# usbtin_clone.net
KiCad netlist of a schematic drawn in EAGLE
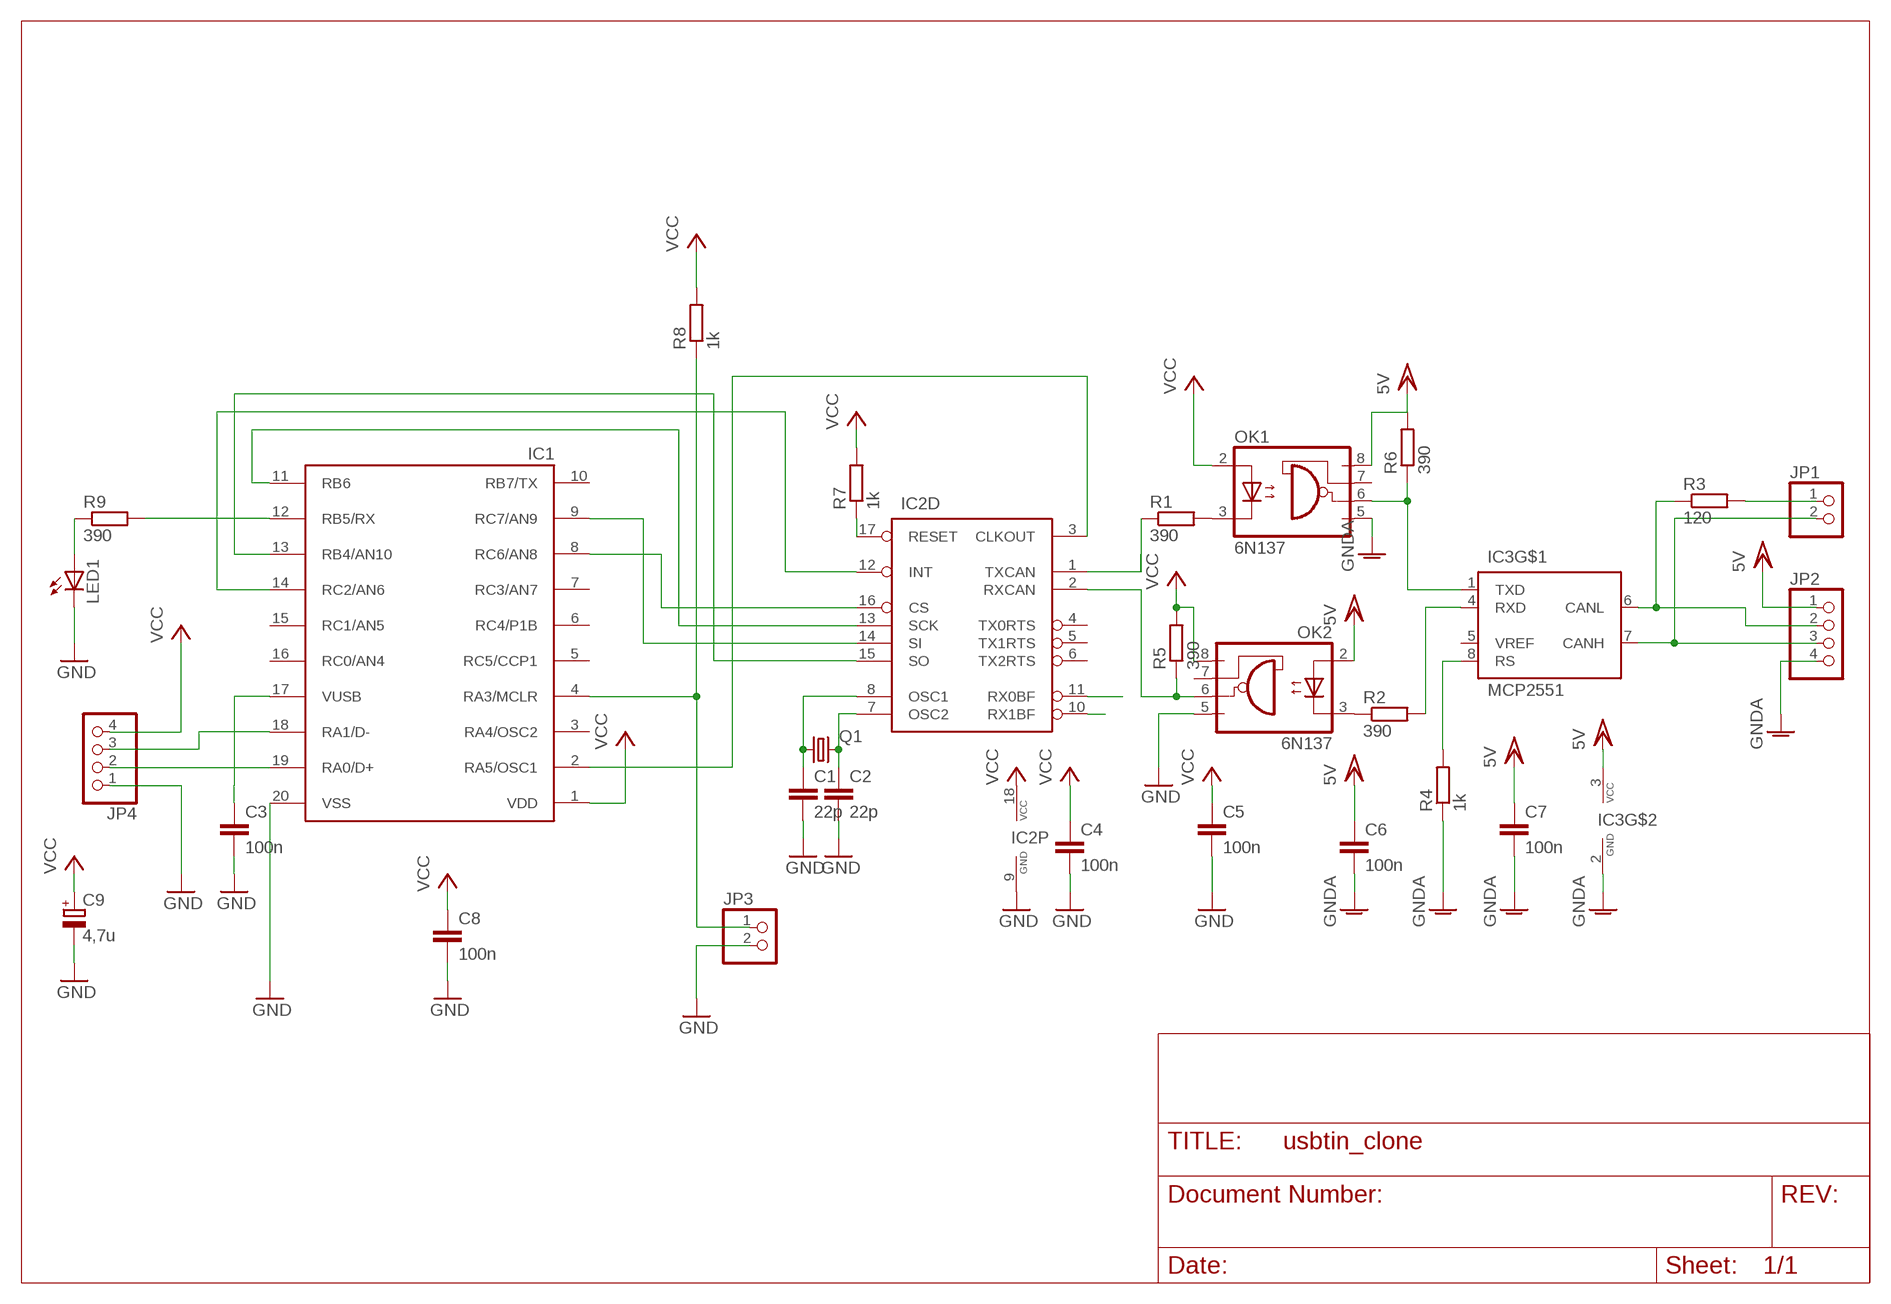
[diagram p0: schematic, sheet 1]

(export (version "E")
  (design (tool "Eeschema 10.0.6"))
  (components
    (comp (ref "C1")
      (value "22p")
      (footprint "eagle-import:C025-025X050")
      (libsource (lib "eagle-import") (part "C-EU025-025X050"))
    )
    (comp (ref "C2")
      (value "22p")
      (footprint "eagle-import:C025-025X050")
      (libsource (lib "eagle-import") (part "C-EU025-025X050"))
    )
    (comp (ref "C3")
      (value "100n")
      (footprint "eagle-import:C025-025X050")
      (libsource (lib "eagle-import") (part "C-EU025-025X050"))
    )
    (comp (ref "C4")
      (value "100n")
      (footprint "eagle-import:C025-025X050")
      (libsource (lib "eagle-import") (part "C-EU025-025X050"))
    )
    (comp (ref "C5")
      (value "100n")
      (footprint "eagle-import:C025-025X050")
      (libsource (lib "eagle-import") (part "C-EU025-025X050"))
    )
    (comp (ref "C6")
      (value "100n")
      (footprint "eagle-import:C025-025X050")
      (libsource (lib "eagle-import") (part "C-EU025-025X050"))
    )
    (comp (ref "C7")
      (value "100n")
      (footprint "eagle-import:C025-025X050")
      (libsource (lib "eagle-import") (part "C-EU025-025X050"))
    )
    (comp (ref "C8")
      (value "100n")
      (footprint "eagle-import:C025-025X050")
      (libsource (lib "eagle-import") (part "C-EU025-025X050"))
    )
    (comp (ref "C9")
      (value "4,7u")
      (footprint "eagle-import:E2,5-5")
      (libsource (lib "eagle-import") (part "CPOL-EUE2.5-5"))
    )
    (comp (ref "IC1")
      (value "18F14K50")
      (footprint "eagle-import:DIL20")
      (libsource (lib "eagle-import") (part "PIC18F14K50"))
    )
    (comp (ref "IC2")
      (value "MCP2515P")
      (footprint "eagle-import:DIL18")
      (libsource (lib "eagle-import") (part "MCP2515P"))
    )
    (comp (ref "IC3")
      (value "MCP2551")
      (footprint "eagle-import:DIL08")
      (libsource (lib "eagle-import") (part "MCP2551DIL8"))
    )
    (comp (ref "JP1")
      (value "PINHD-1X2")
      (footprint "eagle-import:1X02")
      (libsource (lib "eagle-import") (part "PINHD-1X2"))
    )
    (comp (ref "JP2")
      (value "PINHD-1X4")
      (footprint "eagle-import:1X04")
      (libsource (lib "eagle-import") (part "PINHD-1X4"))
    )
    (comp (ref "JP3")
      (value "PINHD-1X2")
      (footprint "eagle-import:1X02")
      (libsource (lib "eagle-import") (part "PINHD-1X2"))
    )
    (comp (ref "JP4")
      (value "PINHD-1X4")
      (footprint "eagle-import:1X04")
      (libsource (lib "eagle-import") (part "PINHD-1X4"))
    )
    (comp (ref "LED1")
      (value "LED3MM")
      (footprint "eagle-import:LED3MM")
      (libsource (lib "eagle-import") (part "LED3MM"))
    )
    (comp (ref "OK1")
      (value "6N137")
      (footprint "eagle-import:DIL08")
      (libsource (lib "eagle-import") (part "6N137"))
    )
    (comp (ref "OK2")
      (value "6N137")
      (footprint "eagle-import:DIL08")
      (libsource (lib "eagle-import") (part "6N137"))
    )
    (comp (ref "Q1")
      (value "CRYSTALHC49S")
      (footprint "eagle-import:HC49_S")
      (libsource (lib "eagle-import") (part "CRYSTALHC49S"))
    )
    (comp (ref "R1")
      (value "390")
      (footprint "eagle-import:0204_7")
      (libsource (lib "eagle-import") (part "R-EU_0204/7"))
    )
    (comp (ref "R2")
      (value "390")
      (footprint "eagle-import:0204_7")
      (libsource (lib "eagle-import") (part "R-EU_0204/7"))
    )
    (comp (ref "R3")
      (value "120")
      (footprint "eagle-import:0204_7")
      (libsource (lib "eagle-import") (part "R-EU_0204/7"))
    )
    (comp (ref "R4")
      (value "1k")
      (footprint "eagle-import:0204_7")
      (libsource (lib "eagle-import") (part "R-EU_0204/7"))
    )
    (comp (ref "R5")
      (value "390")
      (footprint "eagle-import:0204_7")
      (libsource (lib "eagle-import") (part "R-EU_0204/7"))
    )
    (comp (ref "R6")
      (value "390")
      (footprint "eagle-import:0204_7")
      (libsource (lib "eagle-import") (part "R-EU_0204/7"))
    )
    (comp (ref "R7")
      (value "1k")
      (footprint "eagle-import:0204_7")
      (libsource (lib "eagle-import") (part "R-EU_0204/7"))
    )
    (comp (ref "R8")
      (value "1k")
      (footprint "eagle-import:0204_7")
      (libsource (lib "eagle-import") (part "R-EU_0204/7"))
    )
    (comp (ref "R9")
      (value "390")
      (footprint "eagle-import:0204_7")
      (libsource (lib "eagle-import") (part "R-EU_0204/7"))
    )
  )
  (nets
    (net (code "1") (name "5V") (class "Default")
      (node (ref "C6") (pin "1") (pinfunction "1_1") (pintype "passive"))
      (node (ref "C7") (pin "1") (pinfunction "1_1") (pintype "passive"))
      (node (ref "IC3") (pin "3") (pinfunction "VCC_3") (pintype "power_in"))
      (node (ref "JP2") (pin "1") (pinfunction "1_1") (pintype "passive"))
      (node (ref "OK1") (pin "8") (pinfunction "VCC_8") (pintype "passive"))
      (node (ref "OK2") (pin "2") (pinfunction "A_2") (pintype "passive"))
      (node (ref "R6") (pin "2") (pinfunction "2_2") (pintype "passive"))
    )
    (net (code "2") (name "GND") (class "Default")
      (node (ref "C1") (pin "2") (pinfunction "2_2") (pintype "passive"))
      (node (ref "C2") (pin "2") (pinfunction "2_2") (pintype "passive"))
      (node (ref "C3") (pin "2") (pinfunction "2_2") (pintype "passive"))
      (node (ref "C4") (pin "2") (pinfunction "2_2") (pintype "passive"))
      (node (ref "C5") (pin "2") (pinfunction "2_2") (pintype "passive"))
      (node (ref "C8") (pin "2") (pinfunction "2_2") (pintype "passive"))
      (node (ref "C9") (pin "-") (pinfunction "-_-") (pintype "passive"))
      (node (ref "IC1") (pin "20") (pinfunction "VSS_20") (pintype "bidirectional"))
      (node (ref "IC2") (pin "9") (pinfunction "GND_9") (pintype "power_in"))
      (node (ref "JP3") (pin "2") (pinfunction "2_2") (pintype "passive"))
      (node (ref "JP4") (pin "1") (pinfunction "1_1") (pintype "passive"))
      (node (ref "LED1") (pin "K") (pinfunction "C_K") (pintype "passive"))
      (node (ref "OK2") (pin "5") (pinfunction "GND_5") (pintype "passive"))
    )
    (net (code "3") (name "GNDA") (class "Default")
      (node (ref "C6") (pin "2") (pinfunction "2_2") (pintype "passive"))
      (node (ref "C7") (pin "2") (pinfunction "2_2") (pintype "passive"))
      (node (ref "IC3") (pin "2") (pinfunction "GND_2") (pintype "power_in"))
      (node (ref "JP2") (pin "4") (pinfunction "4_4") (pintype "passive"))
      (node (ref "OK1") (pin "5") (pinfunction "GND_5") (pintype "passive"))
      (node (ref "R4") (pin "1") (pinfunction "1_1") (pintype "passive"))
    )
    (net (code "4") (name "Net-(IC1-RA0{slash}D+)") (class "Default")
      (node (ref "IC1") (pin "19") (pinfunction "RA0/D+_19") (pintype "bidirectional"))
      (node (ref "JP4") (pin "2") (pinfunction "2_2") (pintype "passive"))
    )
    (net (code "5") (name "Net-(IC1-RA1{slash}D-)") (class "Default")
      (node (ref "IC1") (pin "18") (pinfunction "RA1/D-_18") (pintype "bidirectional"))
      (node (ref "JP4") (pin "3") (pinfunction "3_3") (pintype "passive"))
    )
    (net (code "6") (name "Net-(IC1-RA3{slash}MCLR)") (class "Default")
      (node (ref "IC1") (pin "4") (pinfunction "RA3/MCLR_4") (pintype "bidirectional"))
      (node (ref "JP3") (pin "1") (pinfunction "1_1") (pintype "passive"))
      (node (ref "R8") (pin "1") (pinfunction "1_1") (pintype "passive"))
    )
    (net (code "7") (name "Net-(IC1-RA5{slash}OSC1)") (class "Default")
      (node (ref "IC1") (pin "2") (pinfunction "RA5/OSC1_2") (pintype "bidirectional"))
      (node (ref "IC2") (pin "3") (pinfunction "CLKOUT_3") (pintype "output"))
    )
    (net (code "8") (name "Net-(IC1-RB4{slash}AN10)") (class "Default")
      (node (ref "IC1") (pin "13") (pinfunction "RB4/AN10_13") (pintype "bidirectional"))
      (node (ref "IC2") (pin "15") (pinfunction "SO_15") (pintype "output"))
    )
    (net (code "9") (name "Net-(IC1-RB5{slash}RX)") (class "Default")
      (node (ref "IC1") (pin "12") (pinfunction "RB5/RX_12") (pintype "bidirectional"))
      (node (ref "R9") (pin "2") (pinfunction "2_2") (pintype "passive"))
    )
    (net (code "10") (name "Net-(IC1-RB6)") (class "Default")
      (node (ref "IC1") (pin "11") (pinfunction "RB6_11") (pintype "bidirectional"))
      (node (ref "IC2") (pin "13") (pinfunction "SCK_13") (pintype "input"))
    )
    (net (code "11") (name "Net-(IC1-RC2{slash}AN6)") (class "Default")
      (node (ref "IC1") (pin "14") (pinfunction "RC2/AN6_14") (pintype "bidirectional"))
      (node (ref "IC2") (pin "12") (pinfunction "INT_12") (pintype "output"))
    )
    (net (code "12") (name "Net-(IC1-RC6{slash}AN8)") (class "Default")
      (node (ref "IC1") (pin "8") (pinfunction "RC6/AN8_8") (pintype "bidirectional"))
      (node (ref "IC2") (pin "16") (pinfunction "CS_16") (pintype "input"))
    )
    (net (code "13") (name "Net-(IC1-RC7{slash}AN9)") (class "Default")
      (node (ref "IC1") (pin "9") (pinfunction "RC7/AN9_9") (pintype "bidirectional"))
      (node (ref "IC2") (pin "14") (pinfunction "SI_14") (pintype "input"))
    )
    (net (code "14") (name "Net-(IC1-VUSB)") (class "Default")
      (node (ref "C3") (pin "1") (pinfunction "1_1") (pintype "passive"))
      (node (ref "IC1") (pin "17") (pinfunction "VUSB_17") (pintype "bidirectional"))
    )
    (net (code "15") (name "Net-(IC2A-OSC1)") (class "Default")
      (node (ref "C1") (pin "1") (pinfunction "1_1") (pintype "passive"))
      (node (ref "IC2") (pin "8") (pinfunction "OSC1_8") (pintype "input"))
      (node (ref "Q1") (pin "1") (pinfunction "1_1") (pintype "passive"))
    )
    (net (code "16") (name "Net-(IC2A-OSC2)") (class "Default")
      (node (ref "C2") (pin "1") (pinfunction "1_1") (pintype "passive"))
      (node (ref "IC2") (pin "7") (pinfunction "OSC2_7") (pintype "input"))
      (node (ref "Q1") (pin "2") (pinfunction "2_2") (pintype "passive"))
    )
    (net (code "17") (name "Net-(IC2A-RESET)") (class "Default")
      (node (ref "IC2") (pin "17") (pinfunction "RESET_17") (pintype "input"))
      (node (ref "R7") (pin "1") (pinfunction "1_1") (pintype "passive"))
    )
    (net (code "18") (name "Net-(IC2A-RXCAN)") (class "Default")
      (node (ref "IC2") (pin "2") (pinfunction "RXCAN_2") (pintype "input"))
      (node (ref "OK2") (pin "6") (pinfunction "VO_6") (pintype "passive"))
      (node (ref "R5") (pin "1") (pinfunction "1_1") (pintype "passive"))
    )
    (net (code "19") (name "Net-(IC2A-TXCAN)") (class "Default")
      (node (ref "IC2") (pin "1") (pinfunction "TXCAN_1") (pintype "output"))
      (node (ref "R1") (pin "1") (pinfunction "1_1") (pintype "passive"))
    )
    (net (code "20") (name "Net-(IC3A-CANH)") (class "Default")
      (node (ref "IC3") (pin "7") (pinfunction "CANH_7") (pintype "bidirectional"))
      (node (ref "JP1") (pin "2") (pinfunction "2_2") (pintype "passive"))
      (node (ref "JP2") (pin "3") (pinfunction "3_3") (pintype "passive"))
    )
    (net (code "21") (name "Net-(IC3A-CANL)") (class "Default")
      (node (ref "IC3") (pin "6") (pinfunction "CANL_6") (pintype "bidirectional"))
      (node (ref "JP2") (pin "2") (pinfunction "2_2") (pintype "passive"))
      (node (ref "R3") (pin "1") (pinfunction "1_1") (pintype "passive"))
    )
    (net (code "22") (name "Net-(IC3A-RS)") (class "Default")
      (node (ref "IC3") (pin "8") (pinfunction "RS_8") (pintype "bidirectional"))
      (node (ref "R4") (pin "2") (pinfunction "2_2") (pintype "passive"))
    )
    (net (code "23") (name "Net-(IC3A-RXD)") (class "Default")
      (node (ref "IC3") (pin "4") (pinfunction "RXD_4") (pintype "bidirectional"))
      (node (ref "R2") (pin "2") (pinfunction "2_2") (pintype "passive"))
    )
    (net (code "24") (name "Net-(IC3A-TXD)") (class "Default")
      (node (ref "IC3") (pin "1") (pinfunction "TXD_1") (pintype "bidirectional"))
      (node (ref "OK1") (pin "6") (pinfunction "VO_6") (pintype "passive"))
      (node (ref "R6") (pin "1") (pinfunction "1_1") (pintype "passive"))
    )
    (net (code "25") (name "Net-(JP1-Pad1)") (class "Default")
      (node (ref "JP1") (pin "1") (pinfunction "1_1") (pintype "passive"))
      (node (ref "R3") (pin "2") (pinfunction "2_2") (pintype "passive"))
    )
    (net (code "26") (name "Net-(LED1-PadA)") (class "Default")
      (node (ref "LED1") (pin "A") (pinfunction "A_A") (pintype "passive"))
      (node (ref "R9") (pin "1") (pinfunction "1_1") (pintype "passive"))
    )
    (net (code "27") (name "Net-(OK1-C)") (class "Default")
      (node (ref "OK1") (pin "3") (pinfunction "C_3") (pintype "passive"))
      (node (ref "R1") (pin "2") (pinfunction "2_2") (pintype "passive"))
    )
    (net (code "28") (name "Net-(OK2-C)") (class "Default")
      (node (ref "OK2") (pin "3") (pinfunction "C_3") (pintype "passive"))
      (node (ref "R2") (pin "1") (pinfunction "1_1") (pintype "passive"))
    )
    (net (code "29") (name "VCC") (class "Default")
      (node (ref "C4") (pin "1") (pinfunction "1_1") (pintype "passive"))
      (node (ref "C5") (pin "1") (pinfunction "1_1") (pintype "passive"))
      (node (ref "C8") (pin "1") (pinfunction "1_1") (pintype "passive"))
      (node (ref "C9") (pin "+") (pinfunction "+_+") (pintype "passive"))
      (node (ref "IC1") (pin "1") (pinfunction "VDD_1") (pintype "bidirectional"))
      (node (ref "IC2") (pin "18") (pinfunction "VCC_18") (pintype "power_in"))
      (node (ref "JP4") (pin "4") (pinfunction "4_4") (pintype "passive"))
      (node (ref "OK1") (pin "2") (pinfunction "A_2") (pintype "passive"))
      (node (ref "OK2") (pin "8") (pinfunction "VCC_8") (pintype "passive"))
      (node (ref "R5") (pin "2") (pinfunction "2_2") (pintype "passive"))
      (node (ref "R7") (pin "2") (pinfunction "2_2") (pintype "passive"))
      (node (ref "R8") (pin "2") (pinfunction "2_2") (pintype "passive"))
    )
    (net (code "30") (name "unconnected-(IC1-RA4{slash}OSC2-Pad3)") (class "Default")
      (node (ref "IC1") (pin "3") (pinfunction "RA4/OSC2_3") (pintype "bidirectional"))
    )
    (net (code "31") (name "unconnected-(IC1-RB7{slash}TX-Pad10)") (class "Default")
      (node (ref "IC1") (pin "10") (pinfunction "RB7/TX_10") (pintype "bidirectional"))
    )
    (net (code "32") (name "unconnected-(IC1-RC0{slash}AN4-Pad16)") (class "Default")
      (node (ref "IC1") (pin "16") (pinfunction "RC0/AN4_16") (pintype "bidirectional"))
    )
    (net (code "33") (name "unconnected-(IC1-RC1{slash}AN5-Pad15)") (class "Default")
      (node (ref "IC1") (pin "15") (pinfunction "RC1/AN5_15") (pintype "bidirectional"))
    )
    (net (code "34") (name "unconnected-(IC1-RC3{slash}AN7-Pad7)") (class "Default")
      (node (ref "IC1") (pin "7") (pinfunction "RC3/AN7_7") (pintype "bidirectional"))
    )
    (net (code "35") (name "unconnected-(IC1-RC4{slash}P1B-Pad6)") (class "Default")
      (node (ref "IC1") (pin "6") (pinfunction "RC4/P1B_6") (pintype "bidirectional"))
    )
    (net (code "36") (name "unconnected-(IC1-RC5{slash}CCP1-Pad5)") (class "Default")
      (node (ref "IC1") (pin "5") (pinfunction "RC5/CCP1_5") (pintype "bidirectional"))
    )
    (net (code "37") (name "unconnected-(IC2A-RX0BF-Pad11)") (class "Default")
      (node (ref "IC2") (pin "11") (pinfunction "RX0BF_11") (pintype "output"))
    )
    (net (code "38") (name "unconnected-(IC2A-RX1BF-Pad10)") (class "Default")
      (node (ref "IC2") (pin "10") (pinfunction "RX1BF_10") (pintype "output"))
    )
    (net (code "39") (name "unconnected-(IC2A-TX0RTS-Pad4)") (class "Default")
      (node (ref "IC2") (pin "4") (pinfunction "TX0RTS_4") (pintype "input"))
    )
    (net (code "40") (name "unconnected-(IC2A-TX1RTS-Pad5)") (class "Default")
      (node (ref "IC2") (pin "5") (pinfunction "TX1RTS_5") (pintype "input"))
    )
    (net (code "41") (name "unconnected-(IC2A-TX2RTS-Pad6)") (class "Default")
      (node (ref "IC2") (pin "6") (pinfunction "TX2RTS_6") (pintype "input"))
    )
    (net (code "42") (name "unconnected-(IC3A-VREF-Pad5)") (class "Default")
      (node (ref "IC3") (pin "5") (pinfunction "VREF_5") (pintype "bidirectional"))
    )
    (net (code "43") (name "unconnected-(OK1-VE-Pad7)") (class "Default")
      (node (ref "OK1") (pin "7") (pinfunction "VE_7") (pintype "passive"))
    )
    (net (code "44") (name "unconnected-(OK2-VE-Pad7)") (class "Default")
      (node (ref "OK2") (pin "7") (pinfunction "VE_7") (pintype "passive"))
    )
  )
)
